# Rs485_Bus_Interface.net
KiCad netlist of a schematic drawn in Altium Designer
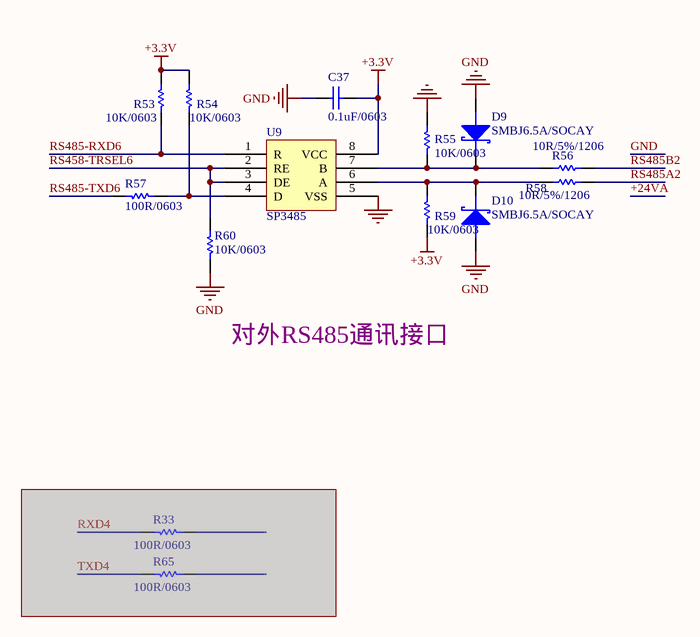
[diagram p0: Rs485_Bus_Interface.SchDoc]

(export (version "E")
  (design (tool "Eeschema 10.0.6"))
  (components
    (comp (ref "C37")
      (value "0.1uF/0603")
      (footprint "CAP/SMT/0603C")
      (libsource (lib "Menred_原理图 封装库") (part "CAP/CAP/SMT/0603C"))
    )
    (comp (ref "D9")
      (value "SMBJ6.5A/SOCAY")
      (footprint "D/SMT/SMBJ4.0A")
      (libsource (lib "Menred_原理图 封装库") (part "D/TVS/SMT/SMBJ6.5A/DO-214"))
    )
    (comp (ref "D10")
      (value "SMBJ6.5A/SOCAY")
      (footprint "D/SMT/SMBJ4.0A")
      (libsource (lib "Menred_原理图 封装库") (part "D/TVS/SMT/SMBJ6.5A/DO-214"))
    )
    (comp (ref "R33")
      (value "100R/0603")
      (footprint "0603R")
      (description "Resistor")
      (fields
        (field (name "MANUFACTURER") "Generic Components")
        (field (name "PUBLISHER") "Altium Hobart Technology Centre")
      )
      (libsource (lib "*") (part "Res1"))
    )
    (comp (ref "R53")
      (value "10K/0603")
      (footprint "0603R")
      (description "Resistor")
      (fields
        (field (name "MANUFACTURER") "Generic Components")
        (field (name "PUBLISHER") "Altium Hobart Technology Centre")
      )
      (libsource (lib "*") (part "Res1"))
    )
    (comp (ref "R54")
      (value "10K/0603")
      (footprint "0603R")
      (description "Resistor")
      (fields
        (field (name "MANUFACTURER") "Generic Components")
        (field (name "PUBLISHER") "Altium Hobart Technology Centre")
      )
      (libsource (lib "*") (part "Res1"))
    )
    (comp (ref "R55")
      (value "10K/0603")
      (footprint "0603R")
      (description "Resistor")
      (fields
        (field (name "MANUFACTURER") "Generic Components")
        (field (name "PUBLISHER") "Altium Hobart Technology Centre")
      )
      (libsource (lib "*") (part "Res1"))
    )
    (comp (ref "R56")
      (value "10R/5%/1206")
      (footprint "1206R")
      (libsource (lib "Menred_原理图 封装库") (part "RES/RES/SMT/1206"))
    )
    (comp (ref "R57")
      (value "100R/0603")
      (footprint "0603R")
      (description "Resistor")
      (fields
        (field (name "MANUFACTURER") "Generic Components")
        (field (name "PUBLISHER") "Altium Hobart Technology Centre")
      )
      (libsource (lib "*") (part "Res1"))
    )
    (comp (ref "R58")
      (value "10R/5%/1206")
      (footprint "1206R")
      (libsource (lib "Menred_原理图 封装库") (part "RES/RES/SMT/1206"))
    )
    (comp (ref "R59")
      (value "10K/0603")
      (footprint "0603R")
      (description "Resistor")
      (fields
        (field (name "MANUFACTURER") "Generic Components")
        (field (name "PUBLISHER") "Altium Hobart Technology Centre")
      )
      (libsource (lib "*") (part "Res1"))
    )
    (comp (ref "R60")
      (value "10K/0603")
      (footprint "0603R")
      (description "Resistor")
      (fields
        (field (name "MANUFACTURER") "Generic Components")
        (field (name "PUBLISHER") "Altium Hobart Technology Centre")
      )
      (libsource (lib "*") (part "Res1"))
    )
    (comp (ref "R65")
      (value "100R/0603")
      (footprint "0603R")
      (description "Resistor")
      (fields
        (field (name "MANUFACTURER") "Generic Components")
        (field (name "PUBLISHER") "Altium Hobart Technology Centre")
      )
      (libsource (lib "*") (part "Res1"))
    )
    (comp (ref "U9") (value "SP3485") (footprint "SOP-8") (libsource (lib "*") (part "MAX487")))
  )
  (nets
    (net (code "1") (name "+3.3V") (class "Default")
      (node (ref "C37") (pin "2") (pinfunction "2_2") (pintype "passive"))
      (node (ref "R53") (pin "2") (pinfunction "2_2") (pintype "passive"))
      (node (ref "R54") (pin "2") (pinfunction "2_2") (pintype "passive"))
      (node (ref "R59") (pin "2") (pinfunction "2_2") (pintype "passive"))
      (node (ref "U9") (pin "8") (pinfunction "VCC_8") (pintype "passive"))
    )
    (net (code "3") (name "/RS458-TRSEL6") (class "Default")
      (node (ref "R60") (pin "2") (pinfunction "2_2") (pintype "passive"))
      (node (ref "U9") (pin "2") (pinfunction "RE_2") (pintype "passive"))
      (node (ref "U9") (pin "3") (pinfunction "DE_3") (pintype "passive"))
    )
    (net (code "4") (name "/RS485-RXD6") (class "Default")
      (node (ref "R53") (pin "1") (pinfunction "1_1") (pintype "passive"))
      (node (ref "U9") (pin "1") (pinfunction "R_1") (pintype "passive"))
    )
    (net (code "5") (name "/RS485-TXD6") (class "Default")
      (node (ref "R57") (pin "2") (pinfunction "2_2") (pintype "passive"))
    )
    (net (code "6") (name "/RS485A2") (class "Default")
      (node (ref "R58") (pin "2") (pinfunction "2_2") (pintype "passive"))
    )
    (net (code "7") (name "/RS485B2") (class "Default")
      (node (ref "R56") (pin "2") (pinfunction "2_2") (pintype "passive"))
    )
    (net (code "8") (name "/RXD4") (class "Default")
      (node (ref "R33") (pin "2") (pinfunction "2_2") (pintype "passive"))
    )
    (net (code "9") (name "/TXD4") (class "Default")
      (node (ref "R65") (pin "2") (pinfunction "2_2") (pintype "passive"))
    )
    (net (code "11") (name "GND") (class "Default")
      (node (ref "C37") (pin "1") (pinfunction "1_1") (pintype "passive"))
      (node (ref "D10") (pin "1") (pinfunction "K_1") (pintype "passive"))
      (node (ref "D9") (pin "1") (pinfunction "K_1") (pintype "passive"))
      (node (ref "R55") (pin "1") (pinfunction "1_1") (pintype "passive"))
      (node (ref "R60") (pin "1") (pinfunction "1_1") (pintype "passive"))
      (node (ref "U9") (pin "5") (pinfunction "VSS_5") (pintype "passive"))
    )
    (net (code "12") (name "Net-(D9-A)") (class "Default")
      (node (ref "D9") (pin "2") (pinfunction "A_2") (pintype "passive"))
      (node (ref "R55") (pin "2") (pinfunction "2_2") (pintype "passive"))
      (node (ref "R56") (pin "1") (pinfunction "1_1") (pintype "passive"))
      (node (ref "U9") (pin "7") (pinfunction "B_7") (pintype "passive"))
    )
    (net (code "13") (name "Net-(D10-A)") (class "Default")
      (node (ref "D10") (pin "2") (pinfunction "A_2") (pintype "passive"))
      (node (ref "R58") (pin "1") (pinfunction "1_1") (pintype "passive"))
      (node (ref "R59") (pin "1") (pinfunction "1_1") (pintype "passive"))
      (node (ref "U9") (pin "6") (pinfunction "A_6") (pintype "passive"))
    )
    (net (code "14") (name "Net-(U9-D)") (class "Default")
      (node (ref "R54") (pin "1") (pinfunction "1_1") (pintype "passive"))
      (node (ref "R57") (pin "1") (pinfunction "1_1") (pintype "passive"))
      (node (ref "U9") (pin "4") (pinfunction "D_4") (pintype "passive"))
    )
    (net (code "15") (name "unconnected-(R33-Pad1)") (class "Default")
      (node (ref "R33") (pin "1") (pinfunction "1_1") (pintype "passive"))
    )
    (net (code "16") (name "unconnected-(R65-Pad1)") (class "Default")
      (node (ref "R65") (pin "1") (pinfunction "1_1") (pintype "passive"))
    )
  )
)
